# MODULIQ_ADC_10Vpp.net
KiCad netlist of a schematic drawn in Altium Designer
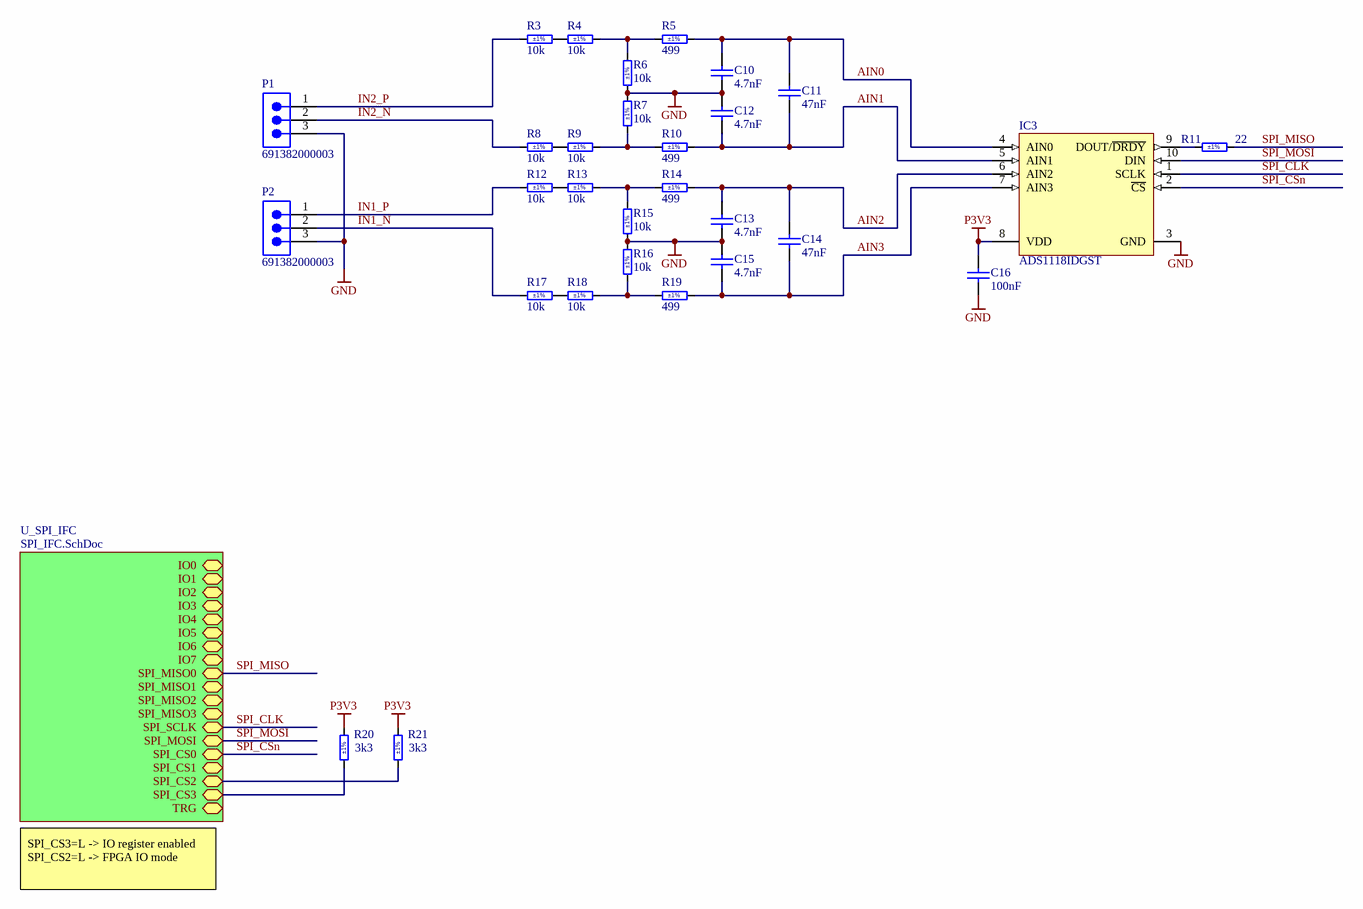
[diagram p0: MODULIQ_ADC_10Vpp.SchDoc]

(export (version "E")
  (design (tool "Eeschema 10.0.6"))
  (components
    (comp (ref "C10")
      (value "4.7nF")
      (footprint "CAPC1005X55N")
      (description "Non-polarised capacitor")
      (fields
        (field (name "PART NUMBER") "CC0402_4.7NF_16V_10%_X7R")
        (field (name "VOLTAGE") "16V")
        (field (name "AUTHOR") "CERN DEM JLC")
      )
      (libsource (lib "Capacitors") (part "Capacitor - non polarized"))
    )
    (comp (ref "C11")
      (value "47nF")
      (footprint "CAPC1005X55N")
      (description "Non-polarised capacitor")
      (fields
        (field (name "PART NUMBER") "CC0402_47NF_25V_10%_X7R")
        (field (name "VOLTAGE") "25V")
        (field (name "AUTHOR") "CERN DEM JLC")
      )
      (libsource (lib "Capacitors") (part "Capacitor - non polarized"))
    )
    (comp (ref "C12")
      (value "4.7nF")
      (footprint "CAPC1005X55N")
      (description "Non-polarised capacitor")
      (fields
        (field (name "PART NUMBER") "CC0402_4.7NF_16V_10%_X7R")
        (field (name "VOLTAGE") "16V")
        (field (name "AUTHOR") "CERN DEM JLC")
      )
      (libsource (lib "Capacitors") (part "Capacitor - non polarized"))
    )
    (comp (ref "C13")
      (value "4.7nF")
      (footprint "CAPC1005X55N")
      (description "Non-polarised capacitor")
      (fields
        (field (name "PART NUMBER") "CC0402_4.7NF_16V_10%_X7R")
        (field (name "VOLTAGE") "16V")
        (field (name "AUTHOR") "CERN DEM JLC")
      )
      (libsource (lib "Capacitors") (part "Capacitor - non polarized"))
    )
    (comp (ref "C14")
      (value "47nF")
      (footprint "CAPC1005X55N")
      (description "Non-polarised capacitor")
      (fields
        (field (name "PART NUMBER") "CC0402_47NF_25V_10%_X7R")
        (field (name "VOLTAGE") "25V")
        (field (name "AUTHOR") "CERN DEM JLC")
      )
      (libsource (lib "Capacitors") (part "Capacitor - non polarized"))
    )
    (comp (ref "C15")
      (value "4.7nF")
      (footprint "CAPC1005X55N")
      (description "Non-polarised capacitor")
      (fields
        (field (name "PART NUMBER") "CC0402_4.7NF_16V_10%_X7R")
        (field (name "VOLTAGE") "16V")
        (field (name "AUTHOR") "CERN DEM JLC")
      )
      (libsource (lib "Capacitors") (part "Capacitor - non polarized"))
    )
    (comp (ref "C16")
      (value "100nF")
      (footprint "CAPC1005X55N")
      (description "Non-polarised capacitor")
      (fields
        (field (name "PART NUMBER") "CC0402_100NF_16V_10%_X7R")
        (field (name "VOLTAGE") "16V")
        (field (name "AUTHOR") "CERN DEM JLC")
      )
      (libsource (lib "Capacitors") (part "Capacitor - non polarized"))
    )
    (comp (ref "IC3")
      (value "ADS1118IDGST")
      (footprint "SOP50P490X110-10N")
      (description "Quad Channel Single ADC Delta-Sigma 860sps 16-bit Serial 10-Pin VSSOP T/R")
      (fields (field (name "MANUFACTURER") "Texas Instruments"))
      (libsource (lib "mb") (part "ADS1118IDGST"))
    )
    (comp (ref "P1")
      (value "691382000003")
      (footprint "691382000003")
      (description "WR-TBL Series 382 Vertical PCB Header, THT, pitch 2.5mm, 3p")
      (fields (field (name "MANUFACTURER") "Wurth Elektronik"))
      (libsource (lib "WE - Electromechanical Components") (part "TBL - 1R - 03P - Male"))
    )
    (comp (ref "P2")
      (value "691382000003")
      (footprint "691382000003")
      (description "WR-TBL Series 382 Vertical PCB Header, THT, pitch 2.5mm, 3p")
      (fields (field (name "MANUFACTURER") "Wurth Elektronik"))
      (libsource (lib "WE - Electromechanical Components") (part "TBL - 1R - 03P - Male"))
    )
    (comp (ref "R3")
      (value "10k")
      (footprint "RESC1005X40N")
      (description "Resistor - 1%")
      (fields
        (field (name "TOLERANCE") "±1%")
        (field (name "PART NUMBER") "R0402_10K_1%_0.0625W_100PPM")
        (field (name "POWER") "0.0625W")
        (field (name "AUTHOR") "CERN DEM JLC")
      )
      (libsource (lib "Resistors") (part "Resistor - 1%"))
    )
    (comp (ref "R4")
      (value "10k")
      (footprint "RESC1005X40N")
      (description "Resistor - 1%")
      (fields
        (field (name "TOLERANCE") "±1%")
        (field (name "PART NUMBER") "R0402_10K_1%_0.0625W_100PPM")
        (field (name "POWER") "0.0625W")
        (field (name "AUTHOR") "CERN DEM JLC")
      )
      (libsource (lib "Resistors") (part "Resistor - 1%"))
    )
    (comp (ref "R5")
      (value "499")
      (footprint "RESC1005X40N")
      (description "Resistor - 1%")
      (fields
        (field (name "TOLERANCE") "±1%")
        (field (name "PART NUMBER") "R0402_499R_1%_0.1W_100PPM")
        (field (name "POWER") "0.1W")
        (field (name "AUTHOR") "CERN DEM MR")
      )
      (libsource (lib "Resistors") (part "Resistor - 1%"))
    )
    (comp (ref "R6")
      (value "10k")
      (footprint "RESC1005X40N")
      (description "Resistor - 1%")
      (fields
        (field (name "TOLERANCE") "±1%")
        (field (name "PART NUMBER") "R0402_10K_1%_0.0625W_100PPM")
        (field (name "POWER") "0.0625W")
        (field (name "AUTHOR") "CERN DEM JLC")
      )
      (libsource (lib "Resistors") (part "Resistor - 1%"))
    )
    (comp (ref "R7")
      (value "10k")
      (footprint "RESC1005X40N")
      (description "Resistor - 1%")
      (fields
        (field (name "TOLERANCE") "±1%")
        (field (name "PART NUMBER") "R0402_10K_1%_0.0625W_100PPM")
        (field (name "POWER") "0.0625W")
        (field (name "AUTHOR") "CERN DEM JLC")
      )
      (libsource (lib "Resistors") (part "Resistor - 1%"))
    )
    (comp (ref "R8")
      (value "10k")
      (footprint "RESC1005X40N")
      (description "Resistor - 1%")
      (fields
        (field (name "TOLERANCE") "±1%")
        (field (name "PART NUMBER") "R0402_10K_1%_0.0625W_100PPM")
        (field (name "POWER") "0.0625W")
        (field (name "AUTHOR") "CERN DEM JLC")
      )
      (libsource (lib "Resistors") (part "Resistor - 1%"))
    )
    (comp (ref "R9")
      (value "10k")
      (footprint "RESC1005X40N")
      (description "Resistor - 1%")
      (fields
        (field (name "TOLERANCE") "±1%")
        (field (name "PART NUMBER") "R0402_10K_1%_0.0625W_100PPM")
        (field (name "POWER") "0.0625W")
        (field (name "AUTHOR") "CERN DEM JLC")
      )
      (libsource (lib "Resistors") (part "Resistor - 1%"))
    )
    (comp (ref "R10")
      (value "499")
      (footprint "RESC1005X40N")
      (description "Resistor - 1%")
      (fields
        (field (name "TOLERANCE") "±1%")
        (field (name "PART NUMBER") "R0402_499R_1%_0.1W_100PPM")
        (field (name "POWER") "0.1W")
        (field (name "AUTHOR") "CERN DEM MR")
      )
      (libsource (lib "Resistors") (part "Resistor - 1%"))
    )
    (comp (ref "R11")
      (value "22")
      (footprint "RESC1005X40N")
      (description "Resistor - 1%")
      (fields
        (field (name "TOLERANCE") "±1%")
        (field (name "PART NUMBER") "R0402_22R_1%_0.0625W_100PPM")
        (field (name "POWER") "0.0625W")
        (field (name "AUTHOR") "CERN DEM JLC")
      )
      (libsource (lib "Resistors") (part "Resistor - 1%"))
    )
    (comp (ref "R12")
      (value "10k")
      (footprint "RESC1005X40N")
      (description "Resistor - 1%")
      (fields
        (field (name "TOLERANCE") "±1%")
        (field (name "PART NUMBER") "R0402_10K_1%_0.0625W_100PPM")
        (field (name "POWER") "0.0625W")
        (field (name "AUTHOR") "CERN DEM JLC")
      )
      (libsource (lib "Resistors") (part "Resistor - 1%"))
    )
    (comp (ref "R13")
      (value "10k")
      (footprint "RESC1005X40N")
      (description "Resistor - 1%")
      (fields
        (field (name "TOLERANCE") "±1%")
        (field (name "PART NUMBER") "R0402_10K_1%_0.0625W_100PPM")
        (field (name "POWER") "0.0625W")
        (field (name "AUTHOR") "CERN DEM JLC")
      )
      (libsource (lib "Resistors") (part "Resistor - 1%"))
    )
    (comp (ref "R14")
      (value "499")
      (footprint "RESC1005X40N")
      (description "Resistor - 1%")
      (fields
        (field (name "TOLERANCE") "±1%")
        (field (name "PART NUMBER") "R0402_499R_1%_0.1W_100PPM")
        (field (name "POWER") "0.1W")
        (field (name "AUTHOR") "CERN DEM MR")
      )
      (libsource (lib "Resistors") (part "Resistor - 1%"))
    )
    (comp (ref "R15")
      (value "10k")
      (footprint "RESC1005X40N")
      (description "Resistor - 1%")
      (fields
        (field (name "TOLERANCE") "±1%")
        (field (name "PART NUMBER") "R0402_10K_1%_0.0625W_100PPM")
        (field (name "POWER") "0.0625W")
        (field (name "AUTHOR") "CERN DEM JLC")
      )
      (libsource (lib "Resistors") (part "Resistor - 1%"))
    )
    (comp (ref "R16")
      (value "10k")
      (footprint "RESC1005X40N")
      (description "Resistor - 1%")
      (fields
        (field (name "TOLERANCE") "±1%")
        (field (name "PART NUMBER") "R0402_10K_1%_0.0625W_100PPM")
        (field (name "POWER") "0.0625W")
        (field (name "AUTHOR") "CERN DEM JLC")
      )
      (libsource (lib "Resistors") (part "Resistor - 1%"))
    )
    (comp (ref "R17")
      (value "10k")
      (footprint "RESC1005X40N")
      (description "Resistor - 1%")
      (fields
        (field (name "TOLERANCE") "±1%")
        (field (name "PART NUMBER") "R0402_10K_1%_0.0625W_100PPM")
        (field (name "POWER") "0.0625W")
        (field (name "AUTHOR") "CERN DEM JLC")
      )
      (libsource (lib "Resistors") (part "Resistor - 1%"))
    )
    (comp (ref "R18")
      (value "10k")
      (footprint "RESC1005X40N")
      (description "Resistor - 1%")
      (fields
        (field (name "TOLERANCE") "±1%")
        (field (name "PART NUMBER") "R0402_10K_1%_0.0625W_100PPM")
        (field (name "POWER") "0.0625W")
        (field (name "AUTHOR") "CERN DEM JLC")
      )
      (libsource (lib "Resistors") (part "Resistor - 1%"))
    )
    (comp (ref "R19")
      (value "499")
      (footprint "RESC1005X40N")
      (description "Resistor - 1%")
      (fields
        (field (name "TOLERANCE") "±1%")
        (field (name "PART NUMBER") "R0402_499R_1%_0.1W_100PPM")
        (field (name "POWER") "0.1W")
        (field (name "AUTHOR") "CERN DEM MR")
      )
      (libsource (lib "Resistors") (part "Resistor - 1%"))
    )
    (comp (ref "R20")
      (value "3k3")
      (footprint "RESC1005X40N")
      (description "Resistor - 1%")
      (fields
        (field (name "TOLERANCE") "±1%")
        (field (name "PART NUMBER") "R0402_3K3_1%_0.0625W_100PPM")
        (field (name "POWER") "0.0625W")
        (field (name "AUTHOR") "CERN DEM JLC")
      )
      (libsource (lib "Resistors") (part "Resistor - 1%"))
    )
    (comp (ref "R21")
      (value "3k3")
      (footprint "RESC1005X40N")
      (description "Resistor - 1%")
      (fields
        (field (name "TOLERANCE") "±1%")
        (field (name "PART NUMBER") "R0402_3K3_1%_0.0625W_100PPM")
        (field (name "POWER") "0.0625W")
        (field (name "AUTHOR") "CERN DEM JLC")
      )
      (libsource (lib "Resistors") (part "Resistor - 1%"))
    )
  )
  (nets
    (net (code "1") (name "/AIN0") (class "Default")
      (node (ref "C10") (pin "2") (pinfunction "2_2") (pintype "passive"))
      (node (ref "C11") (pin "2") (pinfunction "2_2") (pintype "passive"))
      (node (ref "IC3") (pin "4") (pinfunction "AIN0_4") (pintype "input"))
      (node (ref "R5") (pin "2") (pinfunction "2_2") (pintype "passive"))
    )
    (net (code "2") (name "/AIN1") (class "Default")
      (node (ref "C11") (pin "1") (pinfunction "1_1") (pintype "passive"))
      (node (ref "C12") (pin "1") (pinfunction "1_1") (pintype "passive"))
      (node (ref "IC3") (pin "5") (pinfunction "AIN1_5") (pintype "input"))
      (node (ref "R10") (pin "2") (pinfunction "2_2") (pintype "passive"))
    )
    (net (code "3") (name "/AIN2") (class "Default")
      (node (ref "C13") (pin "2") (pinfunction "2_2") (pintype "passive"))
      (node (ref "C14") (pin "2") (pinfunction "2_2") (pintype "passive"))
      (node (ref "IC3") (pin "6") (pinfunction "AIN2_6") (pintype "input"))
      (node (ref "R14") (pin "2") (pinfunction "2_2") (pintype "passive"))
    )
    (net (code "4") (name "/AIN3") (class "Default")
      (node (ref "C14") (pin "1") (pinfunction "1_1") (pintype "passive"))
      (node (ref "C15") (pin "1") (pinfunction "1_1") (pintype "passive"))
      (node (ref "IC3") (pin "7") (pinfunction "AIN3_7") (pintype "input"))
      (node (ref "R19") (pin "2") (pinfunction "2_2") (pintype "passive"))
    )
    (net (code "5") (name "/IN1_N") (class "Default")
      (node (ref "P2") (pin "2") (pinfunction "2_2") (pintype "passive"))
      (node (ref "R17") (pin "2") (pinfunction "2_2") (pintype "passive"))
    )
    (net (code "6") (name "/IN1_P") (class "Default")
      (node (ref "P2") (pin "1") (pinfunction "1_1") (pintype "passive"))
      (node (ref "R12") (pin "2") (pinfunction "2_2") (pintype "passive"))
    )
    (net (code "7") (name "/IN2_N") (class "Default")
      (node (ref "P1") (pin "2") (pinfunction "2_2") (pintype "passive"))
      (node (ref "R8") (pin "2") (pinfunction "2_2") (pintype "passive"))
    )
    (net (code "8") (name "/IN2_P") (class "Default")
      (node (ref "P1") (pin "1") (pinfunction "1_1") (pintype "passive"))
      (node (ref "R3") (pin "2") (pinfunction "2_2") (pintype "passive"))
    )
    (net (code "17") (name "/SPI_CLK") (class "Default")
      (node (ref "IC3") (pin "1") (pinfunction "SCLK_1") (pintype "input"))
    )
    (net (code "19") (name "/SPI_CS2") (class "Default")
      (node (ref "R21") (pin "2") (pinfunction "2_2") (pintype "passive"))
    )
    (net (code "20") (name "/SPI_CS3") (class "Default")
      (node (ref "R20") (pin "2") (pinfunction "2_2") (pintype "passive"))
    )
    (net (code "21") (name "/SPI_CSn") (class "Default")
      (node (ref "IC3") (pin "2") (pinfunction "~{CS}_2") (pintype "input"))
    )
    (net (code "22") (name "/SPI_MISO") (class "Default")
      (node (ref "R11") (pin "2") (pinfunction "2_2") (pintype "passive"))
    )
    (net (code "26") (name "/SPI_MOSI") (class "Default")
      (node (ref "IC3") (pin "10") (pinfunction "DIN_10") (pintype "input"))
    )
    (net (code "28") (name "GND") (class "Default")
      (node (ref "C10") (pin "1") (pinfunction "1_1") (pintype "passive"))
      (node (ref "C12") (pin "2") (pinfunction "2_2") (pintype "passive"))
      (node (ref "C13") (pin "1") (pinfunction "1_1") (pintype "passive"))
      (node (ref "C15") (pin "2") (pinfunction "2_2") (pintype "passive"))
      (node (ref "C16") (pin "1") (pinfunction "1_1") (pintype "passive"))
      (node (ref "IC3") (pin "3") (pinfunction "GND_3") (pintype "power_in"))
      (node (ref "P1") (pin "3") (pinfunction "3_3") (pintype "passive"))
      (node (ref "P2") (pin "3") (pinfunction "3_3") (pintype "passive"))
      (node (ref "R15") (pin "1") (pinfunction "1_1") (pintype "passive"))
      (node (ref "R16") (pin "2") (pinfunction "2_2") (pintype "passive"))
      (node (ref "R6") (pin "1") (pinfunction "1_1") (pintype "passive"))
      (node (ref "R7") (pin "2") (pinfunction "2_2") (pintype "passive"))
    )
    (net (code "29") (name "Net-(IC3-DOUT{slash}~{DRDY})") (class "Default")
      (node (ref "IC3") (pin "9") (pinfunction "DOUT/~{DRDY}_9") (pintype "output"))
      (node (ref "R11") (pin "1") (pinfunction "1_1") (pintype "passive"))
    )
    (net (code "30") (name "Net-(R3-Pad1)") (class "Default")
      (node (ref "R3") (pin "1") (pinfunction "1_1") (pintype "passive"))
      (node (ref "R4") (pin "2") (pinfunction "2_2") (pintype "passive"))
    )
    (net (code "31") (name "Net-(R4-Pad1)") (class "Default")
      (node (ref "R4") (pin "1") (pinfunction "1_1") (pintype "passive"))
      (node (ref "R5") (pin "1") (pinfunction "1_1") (pintype "passive"))
      (node (ref "R6") (pin "2") (pinfunction "2_2") (pintype "passive"))
    )
    (net (code "32") (name "Net-(R8-Pad1)") (class "Default")
      (node (ref "R8") (pin "1") (pinfunction "1_1") (pintype "passive"))
      (node (ref "R9") (pin "2") (pinfunction "2_2") (pintype "passive"))
    )
    (net (code "33") (name "Net-(R10-Pad1)") (class "Default")
      (node (ref "R10") (pin "1") (pinfunction "1_1") (pintype "passive"))
      (node (ref "R7") (pin "1") (pinfunction "1_1") (pintype "passive"))
      (node (ref "R9") (pin "1") (pinfunction "1_1") (pintype "passive"))
    )
    (net (code "34") (name "Net-(R12-Pad1)") (class "Default")
      (node (ref "R12") (pin "1") (pinfunction "1_1") (pintype "passive"))
      (node (ref "R13") (pin "2") (pinfunction "2_2") (pintype "passive"))
    )
    (net (code "35") (name "Net-(R13-Pad1)") (class "Default")
      (node (ref "R13") (pin "1") (pinfunction "1_1") (pintype "passive"))
      (node (ref "R14") (pin "1") (pinfunction "1_1") (pintype "passive"))
      (node (ref "R15") (pin "2") (pinfunction "2_2") (pintype "passive"))
    )
    (net (code "36") (name "Net-(R16-Pad1)") (class "Default")
      (node (ref "R16") (pin "1") (pinfunction "1_1") (pintype "passive"))
      (node (ref "R18") (pin "1") (pinfunction "1_1") (pintype "passive"))
      (node (ref "R19") (pin "1") (pinfunction "1_1") (pintype "passive"))
    )
    (net (code "37") (name "Net-(R17-Pad1)") (class "Default")
      (node (ref "R17") (pin "1") (pinfunction "1_1") (pintype "passive"))
      (node (ref "R18") (pin "2") (pinfunction "2_2") (pintype "passive"))
    )
    (net (code "38") (name "P3V3") (class "Default")
      (node (ref "C16") (pin "2") (pinfunction "2_2") (pintype "passive"))
      (node (ref "IC3") (pin "8") (pinfunction "VDD_8") (pintype "power_in"))
      (node (ref "R20") (pin "1") (pinfunction "1_1") (pintype "passive"))
      (node (ref "R21") (pin "1") (pinfunction "1_1") (pintype "passive"))
    )
  )
)
